# Tachometer-with-4x7-Segm-LED-Display_pcb.net
KiCad netlist of a schematic drawn in EAGLE
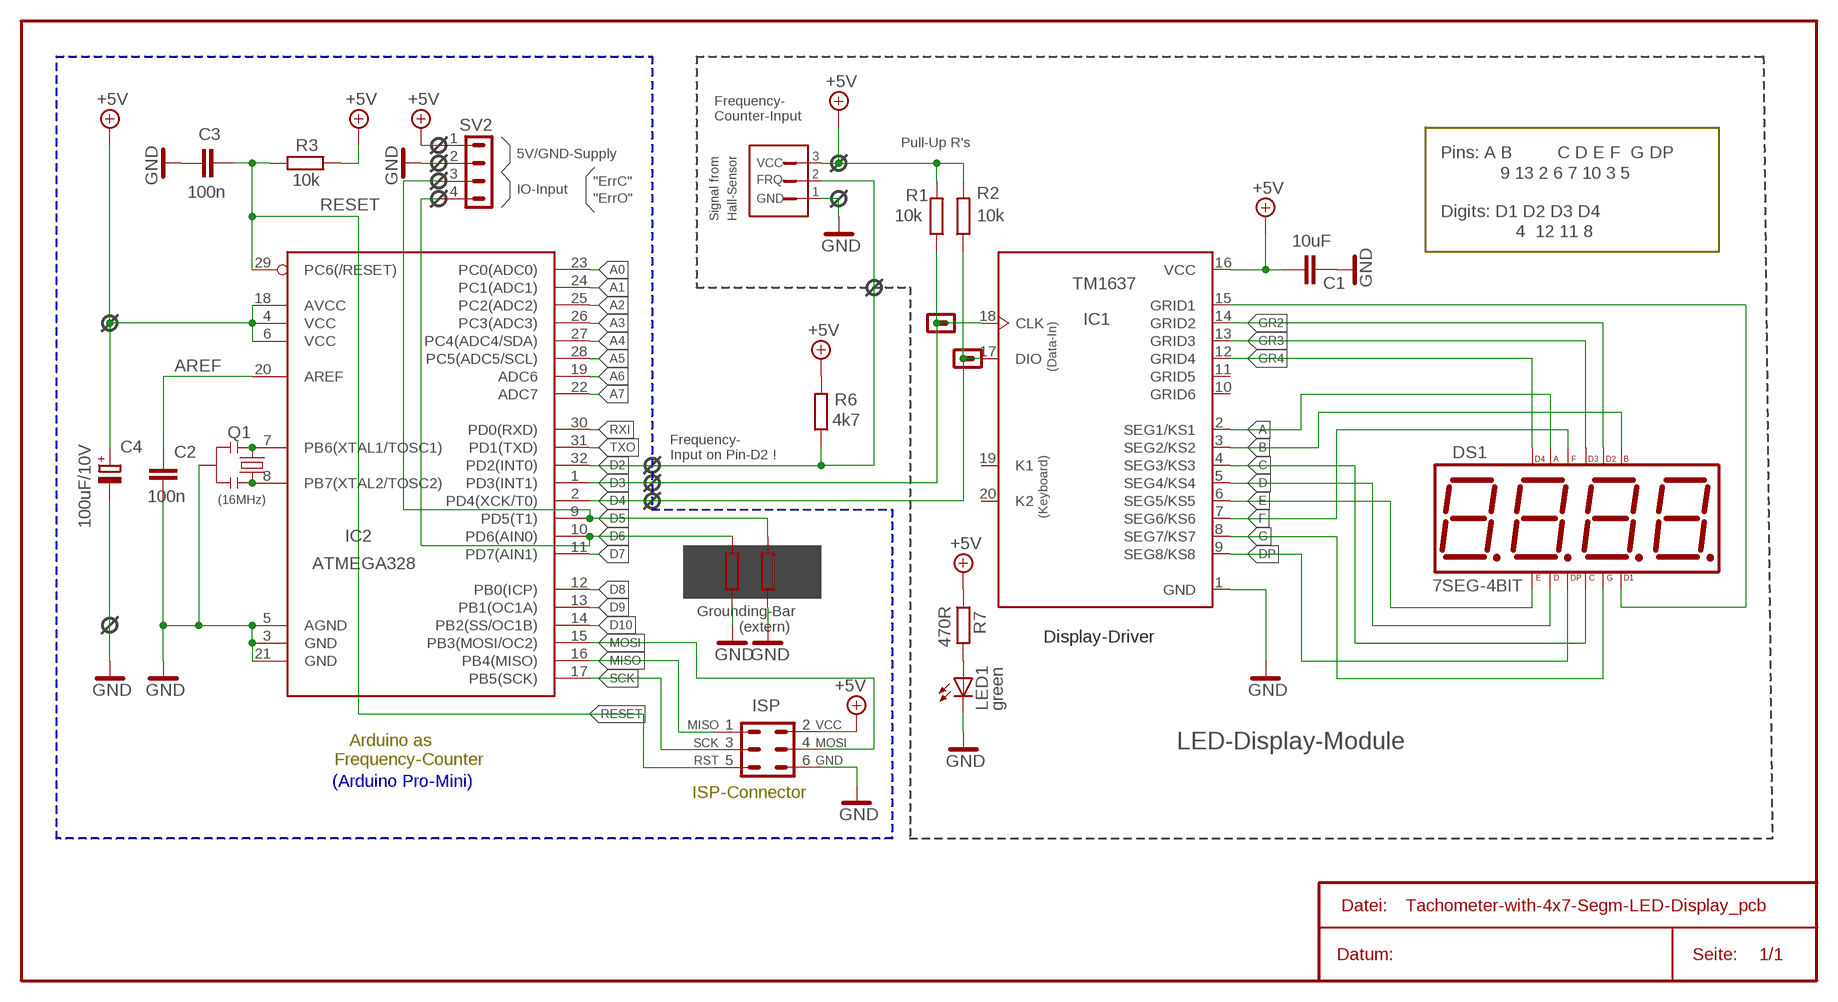
[diagram p0: schematic, sheet 1]

(export (version "E")
  (design (tool "Eeschema 10.0.6"))
  (components
    (comp (ref "C1")
      (value "10uF")
      (footprint "eagle-import:C0805")
      (libsource (lib "eagle-import") (part "C-EUC0805"))
    )
    (comp (ref "C2")
      (value "100n")
      (footprint "eagle-import:C0603")
      (libsource (lib "eagle-import") (part "C-EUC0603"))
    )
    (comp (ref "C3")
      (value "100n")
      (footprint "eagle-import:C0603")
      (libsource (lib "eagle-import") (part "C-EUC0603"))
    )
    (comp (ref "C4")
      (value "100uF/10V")
      (footprint "eagle-import:E2,5-7")
      (libsource (lib "eagle-import") (part "CPOL-EUE2.5-7"))
    )
    (comp (ref "DS1")
      (value "7SEG-4BIT")
      (footprint "eagle-import:7SEG-14-4BIT")
      (libsource (lib "eagle-import") (part "7SEG-4BT"))
    )
    (comp (ref "H")
      (value "Hall-Ss.")
      (footprint "eagle-import:3JST-XH")
      (libsource (lib "eagle-import") (part "3JST-XH"))
    )
    (comp (ref "IC1")
      (value "TM1637")
      (footprint "eagle-import:SOP-20")
      (libsource (lib "eagle-import") (part "TM1637"))
    )
    (comp (ref "IC2")
      (value "ATMEGA328")
      (footprint "eagle-import:TQFP32-08")
      (libsource (lib "eagle-import") (part "ATMEGA168"))
    )
    (comp (ref "ISP")
      (value "MA03-2")
      (footprint "eagle-import:MA03-2")
      (libsource (lib "eagle-import") (part "MA03-2"))
    )
    (comp (ref "LED1")
      (value "green")
      (footprint "eagle-import:CHIPLED_0603")
      (libsource (lib "eagle-import") (part "LEDCHIPLED_0603"))
    )
    (comp (ref "Q1")
      (value "(16MHz)")
      (footprint "eagle-import:RESONATOR-SMD-1_1")
      (libsource (lib "eagle-import") (part "RESONATOR1{colon}1"))
    )
    (comp (ref "R1")
      (value "10k")
      (footprint "eagle-import:R0603")
      (libsource (lib "eagle-import") (part "R-EU_R0603"))
    )
    (comp (ref "R2")
      (value "10k")
      (footprint "eagle-import:R0603")
      (libsource (lib "eagle-import") (part "R-EU_R0603"))
    )
    (comp (ref "R3")
      (value "10k")
      (footprint "eagle-import:R0603")
      (libsource (lib "eagle-import") (part "R-EU_R0603"))
    )
    (comp (ref "R4")
      (value "10k")
      (footprint "eagle-import:R0603")
      (libsource (lib "eagle-import") (part "R-EU_R0603"))
    )
    (comp (ref "R5")
      (value "10k")
      (footprint "eagle-import:R0603")
      (libsource (lib "eagle-import") (part "R-EU_R0603"))
    )
    (comp (ref "R6")
      (value "4k7")
      (footprint "eagle-import:R0603")
      (libsource (lib "eagle-import") (part "R-EU_R0603"))
    )
    (comp (ref "R7")
      (value "470R")
      (footprint "eagle-import:R0603")
      (libsource (lib "eagle-import") (part "R-EU_R0603"))
    )
    (comp (ref "SV2")
      (value "MA04-10")
      (footprint "eagle-import:MA04-1")
      (libsource (lib "eagle-import") (part "MA04-10"))
    )
  )
  (nets
    (net (code "1") (name "+5V") (class "Default")
      (node (ref "C1") (pin "1") (pinfunction "1_1") (pintype "passive"))
      (node (ref "C4") (pin "+") (pinfunction "+_+") (pintype "passive"))
      (node (ref "H") (pin "1") (pinfunction "1_1") (pintype "passive"))
      (node (ref "IC1") (pin "16") (pinfunction "VCC_16") (pintype "bidirectional"))
      (node (ref "IC2") (pin "18") (pinfunction "AVCC_18") (pintype "bidirectional"))
      (node (ref "IC2") (pin "4") (pinfunction "VCC_4") (pintype "bidirectional"))
      (node (ref "IC2") (pin "6") (pinfunction "VCC_6") (pintype "bidirectional"))
      (node (ref "ISP") (pin "2") (pinfunction "2_2") (pintype "passive"))
      (node (ref "R1") (pin "2") (pinfunction "2_2") (pintype "passive"))
      (node (ref "R2") (pin "2") (pinfunction "2_2") (pintype "passive"))
      (node (ref "R3") (pin "2") (pinfunction "2_2") (pintype "passive"))
      (node (ref "R6") (pin "2") (pinfunction "2_2") (pintype "passive"))
      (node (ref "R7") (pin "1") (pinfunction "1_1") (pintype "passive"))
      (node (ref "SV2") (pin "1") (pinfunction "1_1") (pintype "passive"))
    )
    (net (code "2") (name "/AREF") (class "Default")
      (node (ref "C2") (pin "1") (pinfunction "1_1") (pintype "passive"))
      (node (ref "IC2") (pin "20") (pinfunction "AREF_20") (pintype "bidirectional"))
    )
    (net (code "3") (name "A") (class "Default")
      (node (ref "DS1") (pin "A") (pinfunction "A_A") (pintype "bidirectional"))
      (node (ref "IC1") (pin "2") (pinfunction "SEG1/KS1_2") (pintype "bidirectional"))
    )
    (net (code "4") (name "A0") (class "Default")
      (node (ref "IC2") (pin "23") (pinfunction "PC0(ADC0)_23") (pintype "bidirectional"))
    )
    (net (code "5") (name "A1") (class "Default")
      (node (ref "IC2") (pin "24") (pinfunction "PC1(ADC1)_24") (pintype "bidirectional"))
    )
    (net (code "6") (name "A2") (class "Default")
      (node (ref "IC2") (pin "25") (pinfunction "PC2(ADC2)_25") (pintype "bidirectional"))
    )
    (net (code "7") (name "A3") (class "Default")
      (node (ref "IC2") (pin "26") (pinfunction "PC3(ADC3)_26") (pintype "bidirectional"))
    )
    (net (code "8") (name "A4") (class "Default")
      (node (ref "IC2") (pin "27") (pinfunction "PC4(ADC4/SDA)_27") (pintype "bidirectional"))
    )
    (net (code "9") (name "A5") (class "Default")
      (node (ref "IC2") (pin "28") (pinfunction "PC5(ADC5/SCL)_28") (pintype "bidirectional"))
    )
    (net (code "10") (name "A6") (class "Default")
      (node (ref "IC2") (pin "19") (pinfunction "ADC6_19") (pintype "bidirectional"))
    )
    (net (code "11") (name "A7") (class "Default")
      (node (ref "IC2") (pin "22") (pinfunction "ADC7_22") (pintype "bidirectional"))
    )
    (net (code "12") (name "B") (class "Default")
      (node (ref "DS1") (pin "B") (pinfunction "B_B") (pintype "bidirectional"))
      (node (ref "IC1") (pin "3") (pinfunction "SEG2/KS2_3") (pintype "bidirectional"))
    )
    (net (code "13") (name "C") (class "Default")
      (node (ref "DS1") (pin "C") (pinfunction "C_C") (pintype "bidirectional"))
      (node (ref "IC1") (pin "4") (pinfunction "SEG3/KS3_4") (pintype "bidirectional"))
    )
    (net (code "14") (name "D") (class "Default")
      (node (ref "DS1") (pin "D") (pinfunction "D_D") (pintype "bidirectional"))
      (node (ref "IC1") (pin "5") (pinfunction "SEG4/KS4_5") (pintype "bidirectional"))
    )
    (net (code "15") (name "D2") (class "Default")
      (node (ref "H") (pin "2") (pinfunction "1_2") (pintype "passive"))
      (node (ref "IC2") (pin "32") (pinfunction "PD2(INT0)_32") (pintype "bidirectional"))
      (node (ref "R6") (pin "1") (pinfunction "1_1") (pintype "passive"))
    )
    (net (code "16") (name "D3") (class "Default")
      (node (ref "IC1") (pin "18") (pinfunction "CLK_18") (pintype "bidirectional"))
      (node (ref "IC2") (pin "1") (pinfunction "PD3(INT1)_1") (pintype "bidirectional"))
      (node (ref "R1") (pin "1") (pinfunction "1_1") (pintype "passive"))
    )
    (net (code "17") (name "D4") (class "Default")
      (node (ref "IC1") (pin "17") (pinfunction "DIO_17") (pintype "bidirectional"))
      (node (ref "IC2") (pin "2") (pinfunction "PD4(XCK/T0)_2") (pintype "bidirectional"))
      (node (ref "R2") (pin "1") (pinfunction "1_1") (pintype "passive"))
    )
    (net (code "18") (name "D5") (class "Default")
      (node (ref "IC2") (pin "9") (pinfunction "PD5(T1)_9") (pintype "bidirectional"))
      (node (ref "R5") (pin "2") (pinfunction "2_2") (pintype "passive"))
      (node (ref "SV2") (pin "3") (pinfunction "3_3") (pintype "passive"))
    )
    (net (code "19") (name "D6") (class "Default")
      (node (ref "IC2") (pin "10") (pinfunction "PD6(AIN0)_10") (pintype "bidirectional"))
      (node (ref "R4") (pin "2") (pinfunction "2_2") (pintype "passive"))
      (node (ref "SV2") (pin "4") (pinfunction "4_4") (pintype "passive"))
    )
    (net (code "20") (name "D7") (class "Default")
      (node (ref "IC2") (pin "11") (pinfunction "PD7(AIN1)_11") (pintype "bidirectional"))
    )
    (net (code "21") (name "D8") (class "Default")
      (node (ref "IC2") (pin "12") (pinfunction "PB0(ICP)_12") (pintype "bidirectional"))
    )
    (net (code "22") (name "D9") (class "Default")
      (node (ref "IC2") (pin "13") (pinfunction "PB1(OC1A)_13") (pintype "bidirectional"))
    )
    (net (code "23") (name "D10") (class "Default")
      (node (ref "IC2") (pin "14") (pinfunction "PB2(SS/OC1B)_14") (pintype "bidirectional"))
    )
    (net (code "24") (name "DP") (class "Default")
      (node (ref "DS1") (pin "DP") (pinfunction "DP_DP") (pintype "bidirectional"))
      (node (ref "IC1") (pin "9") (pinfunction "SEG8/KS8_9") (pintype "bidirectional"))
    )
    (net (code "25") (name "E") (class "Default")
      (node (ref "DS1") (pin "E") (pinfunction "E_E") (pintype "bidirectional"))
      (node (ref "IC1") (pin "6") (pinfunction "SEG5/KS5_6") (pintype "bidirectional"))
    )
    (net (code "26") (name "F") (class "Default")
      (node (ref "DS1") (pin "F") (pinfunction "F_F") (pintype "bidirectional"))
      (node (ref "IC1") (pin "7") (pinfunction "SEG6/KS6_7") (pintype "bidirectional"))
    )
    (net (code "27") (name "G") (class "Default")
      (node (ref "DS1") (pin "G") (pinfunction "G_G") (pintype "bidirectional"))
      (node (ref "IC1") (pin "8") (pinfunction "SEG7/KS7_8") (pintype "bidirectional"))
    )
    (net (code "28") (name "GND") (class "Default")
      (node (ref "C1") (pin "2") (pinfunction "2_2") (pintype "passive"))
      (node (ref "C2") (pin "2") (pinfunction "2_2") (pintype "passive"))
      (node (ref "C3") (pin "1") (pinfunction "1_1") (pintype "passive"))
      (node (ref "C4") (pin "-") (pinfunction "-_-") (pintype "passive"))
      (node (ref "H") (pin "3") (pinfunction "1_3") (pintype "passive"))
      (node (ref "IC1") (pin "1") (pinfunction "GND_1") (pintype "bidirectional"))
      (node (ref "IC2") (pin "21") (pinfunction "GND_21") (pintype "bidirectional"))
      (node (ref "IC2") (pin "3") (pinfunction "GND_3") (pintype "bidirectional"))
      (node (ref "IC2") (pin "5") (pinfunction "AGND_5") (pintype "bidirectional"))
      (node (ref "ISP") (pin "6") (pinfunction "6_6") (pintype "passive"))
      (node (ref "LED1") (pin "C") (pinfunction "C_C") (pintype "passive"))
      (node (ref "Q1") (pin "2") (pinfunction "2_2") (pintype "passive"))
      (node (ref "R4") (pin "1") (pinfunction "1_1") (pintype "passive"))
      (node (ref "R5") (pin "1") (pinfunction "1_1") (pintype "passive"))
      (node (ref "SV2") (pin "2") (pinfunction "2_2") (pintype "passive"))
    )
    (net (code "29") (name "GR2") (class "Default")
      (node (ref "DS1") (pin "D2") (pinfunction "D2_D2") (pintype "bidirectional"))
      (node (ref "IC1") (pin "14") (pinfunction "GRID2_14") (pintype "bidirectional"))
    )
    (net (code "30") (name "GR3") (class "Default")
      (node (ref "DS1") (pin "D3") (pinfunction "D3_D3") (pintype "bidirectional"))
      (node (ref "IC1") (pin "13") (pinfunction "GRID3_13") (pintype "bidirectional"))
    )
    (net (code "31") (name "GR4") (class "Default")
      (node (ref "DS1") (pin "D4") (pinfunction "D4_D4") (pintype "bidirectional"))
      (node (ref "IC1") (pin "12") (pinfunction "GRID4_12") (pintype "bidirectional"))
    )
    (net (code "32") (name "MISO") (class "Default")
      (node (ref "IC2") (pin "16") (pinfunction "PB4(MISO)_16") (pintype "bidirectional"))
      (node (ref "ISP") (pin "1") (pinfunction "1_1") (pintype "passive"))
    )
    (net (code "33") (name "MOSI") (class "Default")
      (node (ref "IC2") (pin "15") (pinfunction "PB3(MOSI/OC2)_15") (pintype "bidirectional"))
      (node (ref "ISP") (pin "4") (pinfunction "4_4") (pintype "passive"))
    )
    (net (code "34") (name "Net-(IC1-GRID1)") (class "Default")
      (node (ref "DS1") (pin "D1") (pinfunction "D1_D1") (pintype "bidirectional"))
      (node (ref "IC1") (pin "15") (pinfunction "GRID1_15") (pintype "bidirectional"))
    )
    (net (code "35") (name "Net-(IC2-PB6(XTAL1{slash}TOSC1))") (class "Default")
      (node (ref "IC2") (pin "7") (pinfunction "PB6(XTAL1/TOSC1)_7") (pintype "bidirectional"))
      (node (ref "Q1") (pin "1") (pinfunction "1_1") (pintype "passive"))
    )
    (net (code "36") (name "Net-(IC2-PB7(XTAL2{slash}TOSC2))") (class "Default")
      (node (ref "IC2") (pin "8") (pinfunction "PB7(XTAL2/TOSC2)_8") (pintype "bidirectional"))
      (node (ref "Q1") (pin "3") (pinfunction "3_3") (pintype "passive"))
    )
    (net (code "37") (name "Net-(LED1-PadA)") (class "Default")
      (node (ref "LED1") (pin "A") (pinfunction "A_A") (pintype "passive"))
      (node (ref "R7") (pin "2") (pinfunction "2_2") (pintype "passive"))
    )
    (net (code "38") (name "RESET") (class "Default")
      (node (ref "C3") (pin "2") (pinfunction "2_2") (pintype "passive"))
      (node (ref "IC2") (pin "29") (pinfunction "PC6(/RESET)_29") (pintype "bidirectional"))
      (node (ref "ISP") (pin "5") (pinfunction "5_5") (pintype "passive"))
      (node (ref "R3") (pin "1") (pinfunction "1_1") (pintype "passive"))
    )
    (net (code "39") (name "RXI") (class "Default")
      (node (ref "IC2") (pin "30") (pinfunction "PD0(RXD)_30") (pintype "bidirectional"))
    )
    (net (code "40") (name "SCK") (class "Default")
      (node (ref "IC2") (pin "17") (pinfunction "PB5(SCK)_17") (pintype "bidirectional"))
      (node (ref "ISP") (pin "3") (pinfunction "3_3") (pintype "passive"))
    )
    (net (code "41") (name "TXO") (class "Default")
      (node (ref "IC2") (pin "31") (pinfunction "PD1(TXD)_31") (pintype "bidirectional"))
    )
    (net (code "42") (name "unconnected-(IC1-GRID5-Pad11)") (class "Default")
      (node (ref "IC1") (pin "11") (pinfunction "GRID5_11") (pintype "bidirectional"))
    )
    (net (code "43") (name "unconnected-(IC1-GRID6-Pad10)") (class "Default")
      (node (ref "IC1") (pin "10") (pinfunction "GRID6_10") (pintype "bidirectional"))
    )
    (net (code "44") (name "unconnected-(IC1-K1-Pad19)") (class "Default")
      (node (ref "IC1") (pin "19") (pinfunction "K1_19") (pintype "bidirectional"))
    )
    (net (code "45") (name "unconnected-(IC1-K2-Pad20)") (class "Default")
      (node (ref "IC1") (pin "20") (pinfunction "K2_20") (pintype "bidirectional"))
    )
  )
)
